# 701_USBHub-Grid-Part2.net
KiCad netlist of a schematic drawn in Altium Designer
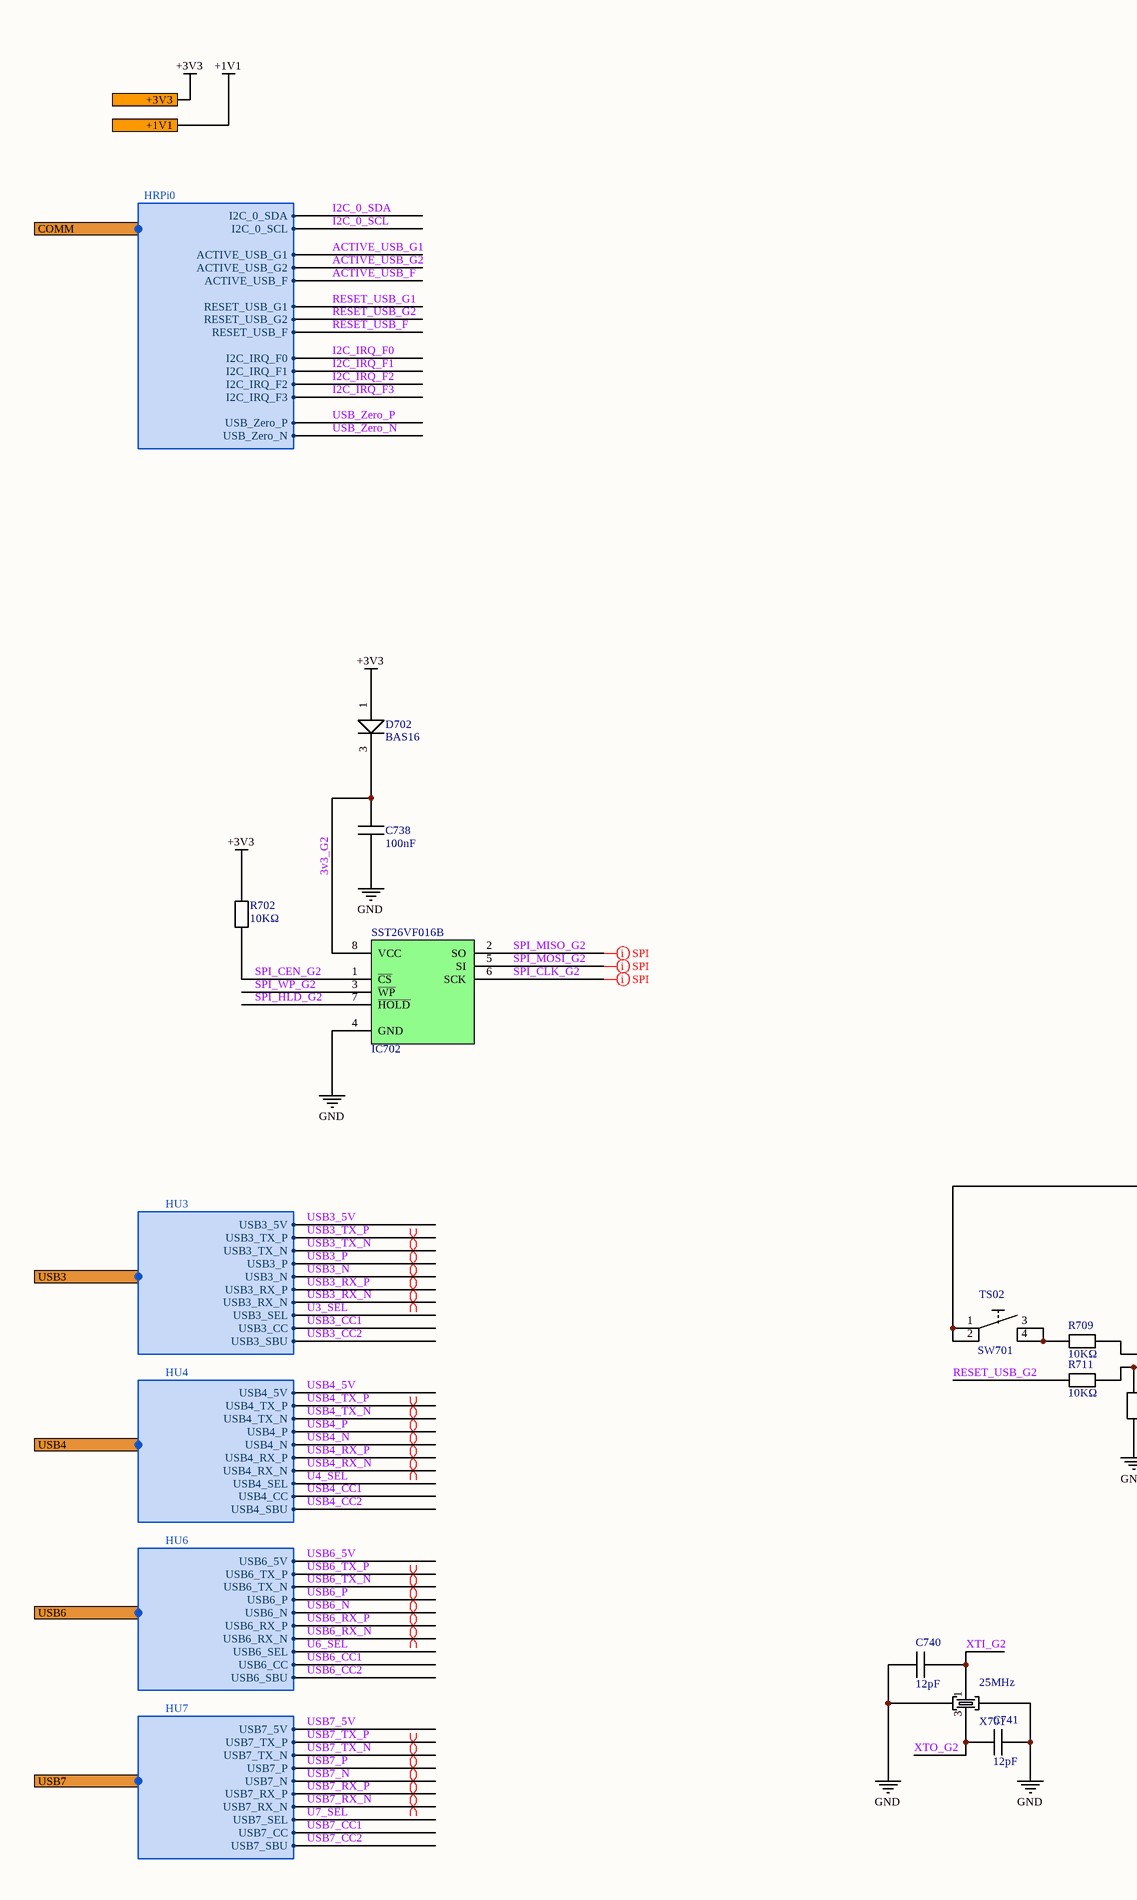
[diagram p0: 701_USBHub-Grid-Part2.SchDoc, left]
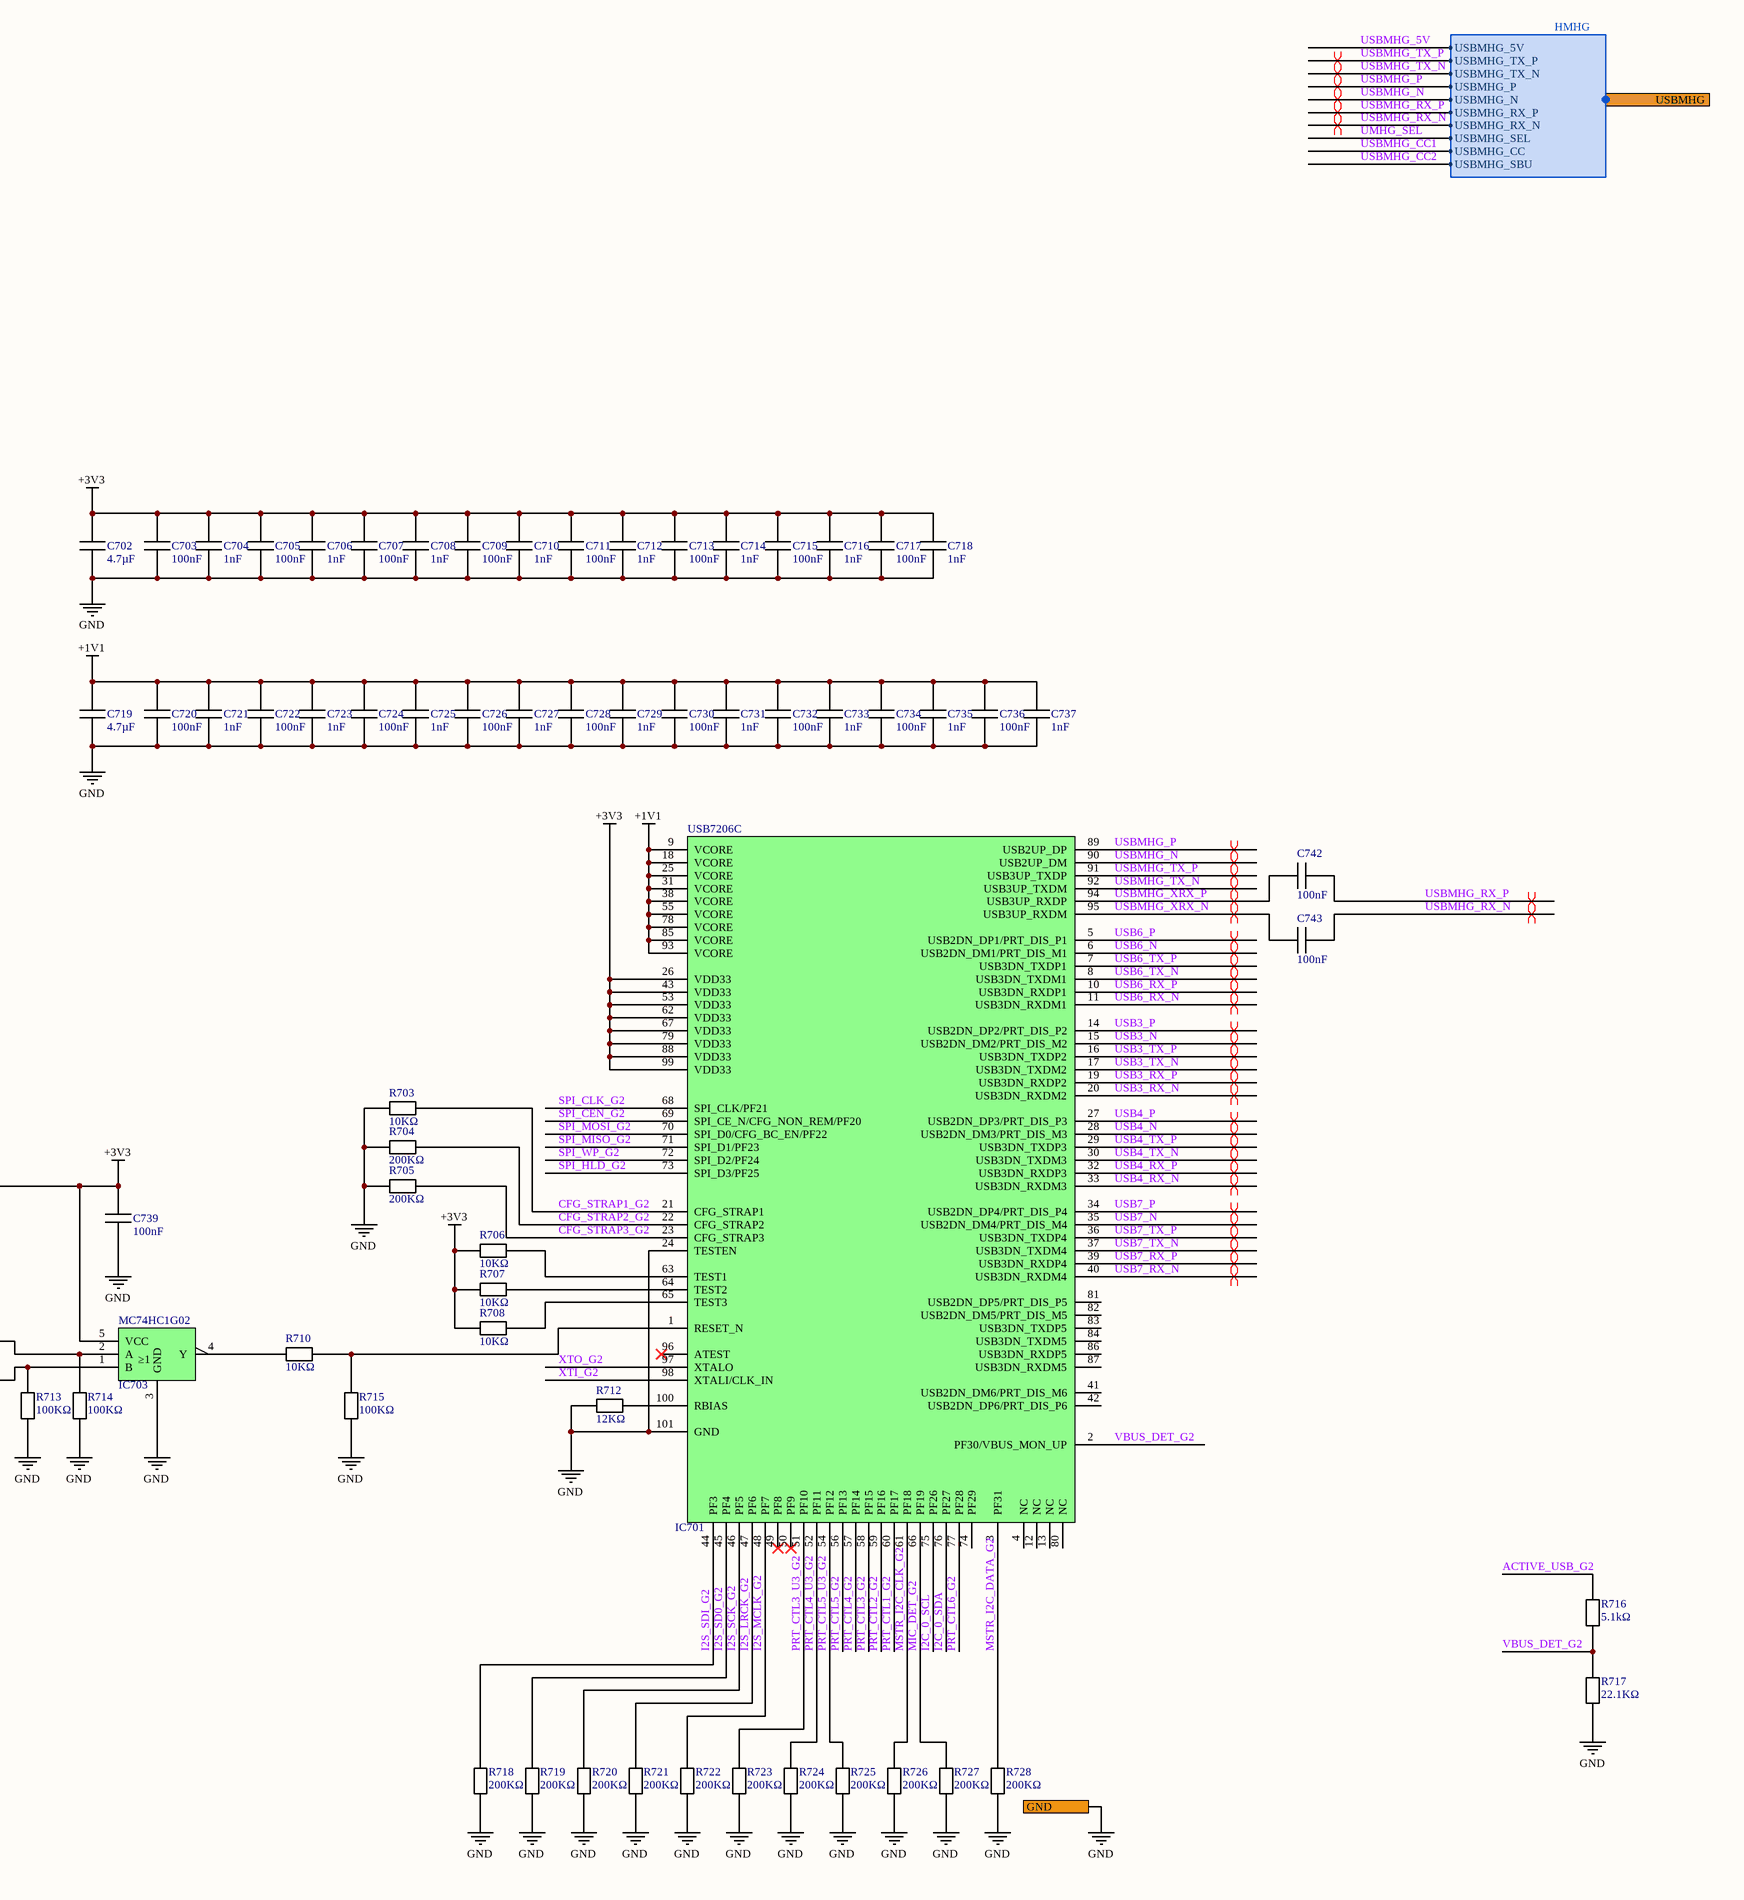
[diagram p1: 701_USBHub-Grid-Part2.SchDoc, right]

(export (version "E")
  (design (tool "Eeschema 10.0.6"))
  (components
    (comp (ref "C702")
      (value "4.7µF")
      (footprint "C0603")
      (description "4.7µF 16V 10% X5R")
      (fields
        (field (name "REFVAL") "4.7µF")
        (field (name "PART NUMBER") "CA0002")
        (field (name "MANFACTPART") "C1608X5R1C475K080AC")
      )
      (libsource (lib "GTS_Database") (part "C"))
    )
    (comp (ref "C703")
      (value "100nF")
      (footprint "C0402")
      (description "100nF 16V 10% X7R")
      (fields
        (field (name "REFVAL") "100nF")
        (field (name "PART NUMBER") "CA0010")
        (field (name "MANFACTPART") "GCM155R71C104KA55D")
      )
      (libsource (lib "GTS_Database") (part "C"))
    )
    (comp (ref "C704")
      (value "1nF")
      (footprint "C0402")
      (description "1nF 50V 1% C0G")
      (fields
        (field (name "REFVAL") "1nF")
        (field (name "PART NUMBER") "CA0031")
        (field (name "MANFACTPART") "GRT1555C1H102FA02D")
      )
      (libsource (lib "GTS_Database") (part "C"))
    )
    (comp (ref "C705")
      (value "100nF")
      (footprint "C0402")
      (description "100nF 16V 10% X7R")
      (fields
        (field (name "REFVAL") "100nF")
        (field (name "PART NUMBER") "CA0010")
        (field (name "MANFACTPART") "GCM155R71C104KA55D")
      )
      (libsource (lib "GTS_Database") (part "C"))
    )
    (comp (ref "C706")
      (value "1nF")
      (footprint "C0402")
      (description "1nF 50V 1% C0G")
      (fields
        (field (name "REFVAL") "1nF")
        (field (name "PART NUMBER") "CA0031")
        (field (name "MANFACTPART") "GRT1555C1H102FA02D")
      )
      (libsource (lib "GTS_Database") (part "C"))
    )
    (comp (ref "C707")
      (value "100nF")
      (footprint "C0402")
      (description "100nF 16V 10% X7R")
      (fields
        (field (name "REFVAL") "100nF")
        (field (name "PART NUMBER") "CA0010")
        (field (name "MANFACTPART") "GCM155R71C104KA55D")
      )
      (libsource (lib "GTS_Database") (part "C"))
    )
    (comp (ref "C708")
      (value "1nF")
      (footprint "C0402")
      (description "1nF 50V 1% C0G")
      (fields
        (field (name "REFVAL") "1nF")
        (field (name "PART NUMBER") "CA0031")
        (field (name "MANFACTPART") "GRT1555C1H102FA02D")
      )
      (libsource (lib "GTS_Database") (part "C"))
    )
    (comp (ref "C709")
      (value "100nF")
      (footprint "C0402")
      (description "100nF 16V 10% X7R")
      (fields
        (field (name "REFVAL") "100nF")
        (field (name "PART NUMBER") "CA0010")
        (field (name "MANFACTPART") "GCM155R71C104KA55D")
      )
      (libsource (lib "GTS_Database") (part "C"))
    )
    (comp (ref "C710")
      (value "1nF")
      (footprint "C0402")
      (description "1nF 50V 1% C0G")
      (fields
        (field (name "REFVAL") "1nF")
        (field (name "PART NUMBER") "CA0031")
        (field (name "MANFACTPART") "GRT1555C1H102FA02D")
      )
      (libsource (lib "GTS_Database") (part "C"))
    )
    (comp (ref "C711")
      (value "100nF")
      (footprint "C0402")
      (description "100nF 16V 10% X7R")
      (fields
        (field (name "REFVAL") "100nF")
        (field (name "PART NUMBER") "CA0010")
        (field (name "MANFACTPART") "GCM155R71C104KA55D")
      )
      (libsource (lib "GTS_Database") (part "C"))
    )
    (comp (ref "C712")
      (value "1nF")
      (footprint "C0402")
      (description "1nF 50V 1% C0G")
      (fields
        (field (name "REFVAL") "1nF")
        (field (name "PART NUMBER") "CA0031")
        (field (name "MANFACTPART") "GRT1555C1H102FA02D")
      )
      (libsource (lib "GTS_Database") (part "C"))
    )
    (comp (ref "C713")
      (value "100nF")
      (footprint "C0402")
      (description "100nF 16V 10% X7R")
      (fields
        (field (name "REFVAL") "100nF")
        (field (name "PART NUMBER") "CA0010")
        (field (name "MANFACTPART") "GCM155R71C104KA55D")
      )
      (libsource (lib "GTS_Database") (part "C"))
    )
    (comp (ref "C714")
      (value "1nF")
      (footprint "C0402")
      (description "1nF 50V 1% C0G")
      (fields
        (field (name "REFVAL") "1nF")
        (field (name "PART NUMBER") "CA0031")
        (field (name "MANFACTPART") "GRT1555C1H102FA02D")
      )
      (libsource (lib "GTS_Database") (part "C"))
    )
    (comp (ref "C715")
      (value "100nF")
      (footprint "C0402")
      (description "100nF 16V 10% X7R")
      (fields
        (field (name "REFVAL") "100nF")
        (field (name "PART NUMBER") "CA0010")
        (field (name "MANFACTPART") "GCM155R71C104KA55D")
      )
      (libsource (lib "GTS_Database") (part "C"))
    )
    (comp (ref "C716")
      (value "1nF")
      (footprint "C0402")
      (description "1nF 50V 1% C0G")
      (fields
        (field (name "REFVAL") "1nF")
        (field (name "PART NUMBER") "CA0031")
        (field (name "MANFACTPART") "GRT1555C1H102FA02D")
      )
      (libsource (lib "GTS_Database") (part "C"))
    )
    (comp (ref "C717")
      (value "100nF")
      (footprint "C0402")
      (description "100nF 16V 10% X7R")
      (fields
        (field (name "REFVAL") "100nF")
        (field (name "PART NUMBER") "CA0010")
        (field (name "MANFACTPART") "GCM155R71C104KA55D")
      )
      (libsource (lib "GTS_Database") (part "C"))
    )
    (comp (ref "C718")
      (value "1nF")
      (footprint "C0402")
      (description "1nF 50V 1% C0G")
      (fields
        (field (name "REFVAL") "1nF")
        (field (name "PART NUMBER") "CA0031")
        (field (name "MANFACTPART") "GRT1555C1H102FA02D")
      )
      (libsource (lib "GTS_Database") (part "C"))
    )
    (comp (ref "C719")
      (value "4.7µF")
      (footprint "C0603")
      (description "4.7µF 16V 10% X5R")
      (fields
        (field (name "REFVAL") "4.7µF")
        (field (name "PART NUMBER") "CA0002")
        (field (name "MANFACTPART") "C1608X5R1C475K080AC")
      )
      (libsource (lib "GTS_Database") (part "C"))
    )
    (comp (ref "C720")
      (value "100nF")
      (footprint "C0402")
      (description "100nF 16V 10% X7R")
      (fields
        (field (name "REFVAL") "100nF")
        (field (name "PART NUMBER") "CA0010")
        (field (name "MANFACTPART") "GCM155R71C104KA55D")
      )
      (libsource (lib "GTS_Database") (part "C"))
    )
    (comp (ref "C721")
      (value "1nF")
      (footprint "C0402")
      (description "1nF 50V 1% C0G")
      (fields
        (field (name "REFVAL") "1nF")
        (field (name "PART NUMBER") "CA0031")
        (field (name "MANFACTPART") "GRT1555C1H102FA02D")
      )
      (libsource (lib "GTS_Database") (part "C"))
    )
    (comp (ref "C722")
      (value "100nF")
      (footprint "C0402")
      (description "100nF 16V 10% X7R")
      (fields
        (field (name "REFVAL") "100nF")
        (field (name "PART NUMBER") "CA0010")
        (field (name "MANFACTPART") "GCM155R71C104KA55D")
      )
      (libsource (lib "GTS_Database") (part "C"))
    )
    (comp (ref "C723")
      (value "1nF")
      (footprint "C0402")
      (description "1nF 50V 1% C0G")
      (fields
        (field (name "REFVAL") "1nF")
        (field (name "PART NUMBER") "CA0031")
        (field (name "MANFACTPART") "GRT1555C1H102FA02D")
      )
      (libsource (lib "GTS_Database") (part "C"))
    )
    (comp (ref "C724")
      (value "100nF")
      (footprint "C0402")
      (description "100nF 16V 10% X7R")
      (fields
        (field (name "REFVAL") "100nF")
        (field (name "PART NUMBER") "CA0010")
        (field (name "MANFACTPART") "GCM155R71C104KA55D")
      )
      (libsource (lib "GTS_Database") (part "C"))
    )
    (comp (ref "C725")
      (value "1nF")
      (footprint "C0402")
      (description "1nF 50V 1% C0G")
      (fields
        (field (name "REFVAL") "1nF")
        (field (name "PART NUMBER") "CA0031")
        (field (name "MANFACTPART") "GRT1555C1H102FA02D")
      )
      (libsource (lib "GTS_Database") (part "C"))
    )
    (comp (ref "C726")
      (value "100nF")
      (footprint "C0402")
      (description "100nF 16V 10% X7R")
      (fields
        (field (name "REFVAL") "100nF")
        (field (name "PART NUMBER") "CA0010")
        (field (name "MANFACTPART") "GCM155R71C104KA55D")
      )
      (libsource (lib "GTS_Database") (part "C"))
    )
    (comp (ref "C727")
      (value "1nF")
      (footprint "C0402")
      (description "1nF 50V 1% C0G")
      (fields
        (field (name "REFVAL") "1nF")
        (field (name "PART NUMBER") "CA0031")
        (field (name "MANFACTPART") "GRT1555C1H102FA02D")
      )
      (libsource (lib "GTS_Database") (part "C"))
    )
    (comp (ref "C728")
      (value "100nF")
      (footprint "C0402")
      (description "100nF 16V 10% X7R")
      (fields
        (field (name "REFVAL") "100nF")
        (field (name "PART NUMBER") "CA0010")
        (field (name "MANFACTPART") "GCM155R71C104KA55D")
      )
      (libsource (lib "GTS_Database") (part "C"))
    )
    (comp (ref "C729")
      (value "1nF")
      (footprint "C0402")
      (description "1nF 50V 1% C0G")
      (fields
        (field (name "REFVAL") "1nF")
        (field (name "PART NUMBER") "CA0031")
        (field (name "MANFACTPART") "GRT1555C1H102FA02D")
      )
      (libsource (lib "GTS_Database") (part "C"))
    )
    (comp (ref "C730")
      (value "100nF")
      (footprint "C0402")
      (description "100nF 16V 10% X7R")
      (fields
        (field (name "REFVAL") "100nF")
        (field (name "PART NUMBER") "CA0010")
        (field (name "MANFACTPART") "GCM155R71C104KA55D")
      )
      (libsource (lib "GTS_Database") (part "C"))
    )
    (comp (ref "C731")
      (value "1nF")
      (footprint "C0402")
      (description "1nF 50V 1% C0G")
      (fields
        (field (name "REFVAL") "1nF")
        (field (name "PART NUMBER") "CA0031")
        (field (name "MANFACTPART") "GRT1555C1H102FA02D")
      )
      (libsource (lib "GTS_Database") (part "C"))
    )
    (comp (ref "C732")
      (value "100nF")
      (footprint "C0402")
      (description "100nF 16V 10% X7R")
      (fields
        (field (name "REFVAL") "100nF")
        (field (name "PART NUMBER") "CA0010")
        (field (name "MANFACTPART") "GCM155R71C104KA55D")
      )
      (libsource (lib "GTS_Database") (part "C"))
    )
    (comp (ref "C733")
      (value "1nF")
      (footprint "C0402")
      (description "1nF 50V 1% C0G")
      (fields
        (field (name "REFVAL") "1nF")
        (field (name "PART NUMBER") "CA0031")
        (field (name "MANFACTPART") "GRT1555C1H102FA02D")
      )
      (libsource (lib "GTS_Database") (part "C"))
    )
    (comp (ref "C734")
      (value "100nF")
      (footprint "C0402")
      (description "100nF 16V 10% X7R")
      (fields
        (field (name "REFVAL") "100nF")
        (field (name "PART NUMBER") "CA0010")
        (field (name "MANFACTPART") "GCM155R71C104KA55D")
      )
      (libsource (lib "GTS_Database") (part "C"))
    )
    (comp (ref "C735")
      (value "1nF")
      (footprint "C0402")
      (description "1nF 50V 1% C0G")
      (fields
        (field (name "REFVAL") "1nF")
        (field (name "PART NUMBER") "CA0031")
        (field (name "MANFACTPART") "GRT1555C1H102FA02D")
      )
      (libsource (lib "GTS_Database") (part "C"))
    )
    (comp (ref "C736")
      (value "100nF")
      (footprint "C0402")
      (description "100nF 16V 10% X7R")
      (fields
        (field (name "REFVAL") "100nF")
        (field (name "PART NUMBER") "CA0010")
        (field (name "MANFACTPART") "GCM155R71C104KA55D")
      )
      (libsource (lib "GTS_Database") (part "C"))
    )
    (comp (ref "C737")
      (value "1nF")
      (footprint "C0402")
      (description "1nF 50V 1% C0G")
      (fields
        (field (name "REFVAL") "1nF")
        (field (name "PART NUMBER") "CA0031")
        (field (name "MANFACTPART") "GRT1555C1H102FA02D")
      )
      (libsource (lib "GTS_Database") (part "C"))
    )
    (comp (ref "C738")
      (value "100nF")
      (footprint "C0402")
      (description "100nF 16V 10% X7R")
      (fields
        (field (name "REFVAL") "100nF")
        (field (name "PART NUMBER") "CA0010")
        (field (name "MANFACTPART") "GCM155R71C104KA55D")
      )
      (libsource (lib "GTS_Database") (part "C"))
    )
    (comp (ref "C739")
      (value "100nF")
      (footprint "C0402")
      (description "100nF 16V 10% X7R")
      (fields
        (field (name "REFVAL") "100nF")
        (field (name "PART NUMBER") "CA0010")
        (field (name "MANFACTPART") "GCM155R71C104KA55D")
      )
      (libsource (lib "GTS_Database") (part "C"))
    )
    (comp (ref "C740")
      (value "12pF")
      (footprint "C0402")
      (description "12pF 16V 1% C0G")
      (fields
        (field (name "REFVAL") "12pF")
        (field (name "PART NUMBER") "CA0059")
        (field (name "MANFACTPART") "VJ0402A120FXJCW1BC")
      )
      (libsource (lib "GTS_Database") (part "C"))
    )
    (comp (ref "C741")
      (value "12pF")
      (footprint "C0402")
      (description "12pF 16V 1% C0G")
      (fields
        (field (name "REFVAL") "12pF")
        (field (name "PART NUMBER") "CA0059")
        (field (name "MANFACTPART") "VJ0402A120FXJCW1BC")
      )
      (libsource (lib "GTS_Database") (part "C"))
    )
    (comp (ref "C742")
      (value "100nF")
      (footprint "C0402")
      (description "100nF 16V 10% X7R")
      (fields
        (field (name "REFVAL") "100nF")
        (field (name "PART NUMBER") "CA0010")
        (field (name "MANFACTPART") "GCM155R71C104KA55D")
      )
      (libsource (lib "GTS_Database") (part "C"))
    )
    (comp (ref "C743")
      (value "100nF")
      (footprint "C0402")
      (description "100nF 16V 10% X7R")
      (fields
        (field (name "REFVAL") "100nF")
        (field (name "PART NUMBER") "CA0010")
        (field (name "MANFACTPART") "GCM155R71C104KA55D")
      )
      (libsource (lib "GTS_Database") (part "C"))
    )
    (comp (ref "D702")
      (value "BAS16")
      (footprint "SOT-23")
      (description "Diodes - General Purpose, Power, Switching 100Vll Signal Switching Diodes 2A")
      (fields
        (field (name "REFVAL") "BAS16")
        (field (name "PART NUMBER") "DI0010")
        (field (name "MANFACTPART") "BAS16_R1_00001")
      )
      (libsource (lib "GTS_Database") (part "Ddefault_3P"))
    )
    (comp (ref "IC701")
      (value "USB7206C")
      (footprint "VQFN-100G_12X12")
      (description "6-Port USB 3.2 Gen 2 Controller Hub")
      (fields (field (name "REFVAL") "USB7206C") (field (name "PART NUMBER") "IC0065"))
      (libsource (lib "GTS_Database") (part "USB7206C"))
    )
    (comp (ref "IC702")
      (value "SST26VF016B")
      (footprint "SO-8")
      (description "16 Mbit Serial Quad I/O (SQI) Flash Memory")
      (fields
        (field (name "REFVAL") "SST26VF016B")
        (field (name "PART NUMBER") "IC0059")
        (field (name "MANFACTPART") "SST26VF016B-104I/SM")
      )
      (libsource (lib "GTS_Database") (part "SST26VF016B"))
    )
    (comp (ref "IC703")
      (value "MC74HC1G02")
      (footprint "TSOP-5")
      (description "Logic Gates 2-6V Single 2-Input NOR")
      (fields
        (field (name "REFVAL") "MC74HC1G02")
        (field (name "PART NUMBER") "IC0061")
        (field (name "MANFACTPART") "MC74HC1G02DTT1G")
      )
      (libsource (lib "GTS_Database") (part "MC74HC1G02"))
    )
    (comp (ref "R702")
      (value "10KΩ")
      (footprint "R0402")
      (description "10KΩ 1% 62.5mW")
      (fields
        (field (name "REFVAL") "10KΩ")
        (field (name "PART NUMBER") "RS0011")
        (field (name "MANFACTPART") "WR04X1002FTL")
      )
      (libsource (lib "GTS_Database") (part "R"))
    )
    (comp (ref "R703")
      (value "10KΩ")
      (footprint "R0402")
      (description "10KΩ 1% 62.5mW")
      (fields
        (field (name "REFVAL") "10KΩ")
        (field (name "PART NUMBER") "RS0011")
        (field (name "MANFACTPART") "WR04X1002FTL")
      )
      (libsource (lib "GTS_Database") (part "R"))
    )
    (comp (ref "R704")
      (value "200KΩ")
      (footprint "R0402")
      (description "200KΩ 1% 62.5mW 100PPM")
      (fields
        (field (name "REFVAL") "200KΩ")
        (field (name "PART NUMBER") "RS0045")
        (field (name "MANFACTPART") "CRG0402F200K")
      )
      (libsource (lib "GTS_Database") (part "R"))
    )
    (comp (ref "R705")
      (value "200KΩ")
      (footprint "R0402")
      (description "200KΩ 1% 62.5mW 100PPM")
      (fields
        (field (name "REFVAL") "200KΩ")
        (field (name "PART NUMBER") "RS0045")
        (field (name "MANFACTPART") "CRG0402F200K")
      )
      (libsource (lib "GTS_Database") (part "R"))
    )
    (comp (ref "R706")
      (value "10KΩ")
      (footprint "R0402")
      (description "10KΩ 1% 62.5mW")
      (fields
        (field (name "REFVAL") "10KΩ")
        (field (name "PART NUMBER") "RS0011")
        (field (name "MANFACTPART") "WR04X1002FTL")
      )
      (libsource (lib "GTS_Database") (part "R"))
    )
    (comp (ref "R707")
      (value "10KΩ")
      (footprint "R0402")
      (description "10KΩ 1% 62.5mW")
      (fields
        (field (name "REFVAL") "10KΩ")
        (field (name "PART NUMBER") "RS0011")
        (field (name "MANFACTPART") "WR04X1002FTL")
      )
      (libsource (lib "GTS_Database") (part "R"))
    )
    (comp (ref "R708")
      (value "10KΩ")
      (footprint "R0402")
      (description "10KΩ 1% 62.5mW")
      (fields
        (field (name "REFVAL") "10KΩ")
        (field (name "PART NUMBER") "RS0011")
        (field (name "MANFACTPART") "WR04X1002FTL")
      )
      (libsource (lib "GTS_Database") (part "R"))
    )
    (comp (ref "R709")
      (value "10KΩ")
      (footprint "R0402")
      (description "10KΩ 1% 62.5mW")
      (fields
        (field (name "REFVAL") "10KΩ")
        (field (name "PART NUMBER") "RS0011")
        (field (name "MANFACTPART") "WR04X1002FTL")
      )
      (libsource (lib "GTS_Database") (part "R"))
    )
    (comp (ref "R710")
      (value "10KΩ")
      (footprint "R0402")
      (description "10KΩ 1% 62.5mW")
      (fields
        (field (name "REFVAL") "10KΩ")
        (field (name "PART NUMBER") "RS0011")
        (field (name "MANFACTPART") "WR04X1002FTL")
      )
      (libsource (lib "GTS_Database") (part "R"))
    )
    (comp (ref "R711")
      (value "10KΩ")
      (footprint "R0402")
      (description "10KΩ 1% 62.5mW")
      (fields
        (field (name "REFVAL") "10KΩ")
        (field (name "PART NUMBER") "RS0011")
        (field (name "MANFACTPART") "WR04X1002FTL")
      )
      (libsource (lib "GTS_Database") (part "R"))
    )
    (comp (ref "R712")
      (value "12KΩ")
      (footprint "R0402")
      (description "12KΩ 1% 62.5mW")
      (fields
        (field (name "REFVAL") "12KΩ")
        (field (name "PART NUMBER") "RS0015")
        (field (name "MANFACTPART") "RC0402FR-1312KL")
      )
      (libsource (lib "GTS_Database") (part "R"))
    )
    (comp (ref "R713")
      (value "100KΩ")
      (footprint "R0402")
      (description "100KΩ 1% 62.5mW 100PPM")
      (fields
        (field (name "REFVAL") "100KΩ")
        (field (name "PART NUMBER") "RS0036")
        (field (name "MANFACTPART") "AC0402FR-13100KL")
      )
      (libsource (lib "GTS_Database") (part "R"))
    )
    (comp (ref "R714")
      (value "100KΩ")
      (footprint "R0402")
      (description "100KΩ 1% 62.5mW 100PPM")
      (fields
        (field (name "REFVAL") "100KΩ")
        (field (name "PART NUMBER") "RS0036")
        (field (name "MANFACTPART") "AC0402FR-13100KL")
      )
      (libsource (lib "GTS_Database") (part "R"))
    )
    (comp (ref "R715")
      (value "100KΩ")
      (footprint "R0402")
      (description "100KΩ 1% 62.5mW 100PPM")
      (fields
        (field (name "REFVAL") "100KΩ")
        (field (name "PART NUMBER") "RS0036")
        (field (name "MANFACTPART") "AC0402FR-13100KL")
      )
      (libsource (lib "GTS_Database") (part "R"))
    )
    (comp (ref "R716")
      (value "5.1kΩ")
      (footprint "R0402")
      (description "5.1KΩ 1% 62.5mW 100PPM")
      (fields
        (field (name "REFVAL") "5.1kΩ")
        (field (name "PART NUMBER") "RS0038")
        (field (name "MANFACTPART") "CRCW04025K10FKEDC")
      )
      (libsource (lib "GTS_Database") (part "R"))
    )
    (comp (ref "R717")
      (value "22.1KΩ")
      (footprint "R0603")
      (description "22.1KΩ 1% 100mW 100PPM")
      (fields
        (field (name "REFVAL") "22.1KΩ")
        (field (name "PART NUMBER") "RS0040")
        (field (name "MANFACTPART") "RC0603FR-0722K1L")
      )
      (libsource (lib "GTS_Database") (part "R"))
    )
    (comp (ref "R718")
      (value "200KΩ")
      (footprint "R0402")
      (description "200KΩ 1% 62.5mW 100PPM")
      (fields
        (field (name "REFVAL") "200KΩ")
        (field (name "PART NUMBER") "RS0045")
        (field (name "MANFACTPART") "CRG0402F200K")
      )
      (libsource (lib "GTS_Database") (part "R"))
    )
    (comp (ref "R719")
      (value "200KΩ")
      (footprint "R0402")
      (description "200KΩ 1% 62.5mW 100PPM")
      (fields
        (field (name "REFVAL") "200KΩ")
        (field (name "PART NUMBER") "RS0045")
        (field (name "MANFACTPART") "CRG0402F200K")
      )
      (libsource (lib "GTS_Database") (part "R"))
    )
    (comp (ref "R720")
      (value "200KΩ")
      (footprint "R0402")
      (description "200KΩ 1% 62.5mW 100PPM")
      (fields
        (field (name "REFVAL") "200KΩ")
        (field (name "PART NUMBER") "RS0045")
        (field (name "MANFACTPART") "CRG0402F200K")
      )
      (libsource (lib "GTS_Database") (part "R"))
    )
    (comp (ref "R721")
      (value "200KΩ")
      (footprint "R0402")
      (description "200KΩ 1% 62.5mW 100PPM")
      (fields
        (field (name "REFVAL") "200KΩ")
        (field (name "PART NUMBER") "RS0045")
        (field (name "MANFACTPART") "CRG0402F200K")
      )
      (libsource (lib "GTS_Database") (part "R"))
    )
    (comp (ref "R722")
      (value "200KΩ")
      (footprint "R0402")
      (description "200KΩ 1% 62.5mW 100PPM")
      (fields
        (field (name "REFVAL") "200KΩ")
        (field (name "PART NUMBER") "RS0045")
        (field (name "MANFACTPART") "CRG0402F200K")
      )
      (libsource (lib "GTS_Database") (part "R"))
    )
    (comp (ref "R723")
      (value "200KΩ")
      (footprint "R0402")
      (description "200KΩ 1% 62.5mW 100PPM")
      (fields
        (field (name "REFVAL") "200KΩ")
        (field (name "PART NUMBER") "RS0045")
        (field (name "MANFACTPART") "CRG0402F200K")
      )
      (libsource (lib "GTS_Database") (part "R"))
    )
    (comp (ref "R724")
      (value "200KΩ")
      (footprint "R0402")
      (description "200KΩ 1% 62.5mW 100PPM")
      (fields
        (field (name "REFVAL") "200KΩ")
        (field (name "PART NUMBER") "RS0045")
        (field (name "MANFACTPART") "CRG0402F200K")
      )
      (libsource (lib "GTS_Database") (part "R"))
    )
    (comp (ref "R725")
      (value "200KΩ")
      (footprint "R0402")
      (description "200KΩ 1% 62.5mW 100PPM")
      (fields
        (field (name "REFVAL") "200KΩ")
        (field (name "PART NUMBER") "RS0045")
        (field (name "MANFACTPART") "CRG0402F200K")
      )
      (libsource (lib "GTS_Database") (part "R"))
    )
    (comp (ref "R726")
      (value "200KΩ")
      (footprint "R0402")
      (description "200KΩ 1% 62.5mW 100PPM")
      (fields
        (field (name "REFVAL") "200KΩ")
        (field (name "PART NUMBER") "RS0045")
        (field (name "MANFACTPART") "CRG0402F200K")
      )
      (libsource (lib "GTS_Database") (part "R"))
    )
    (comp (ref "R727")
      (value "200KΩ")
      (footprint "R0402")
      (description "200KΩ 1% 62.5mW 100PPM")
      (fields
        (field (name "REFVAL") "200KΩ")
        (field (name "PART NUMBER") "RS0045")
        (field (name "MANFACTPART") "CRG0402F200K")
      )
      (libsource (lib "GTS_Database") (part "R"))
    )
    (comp (ref "R728")
      (value "200KΩ")
      (footprint "R0402")
      (description "200KΩ 1% 62.5mW 100PPM")
      (fields
        (field (name "REFVAL") "200KΩ")
        (field (name "PART NUMBER") "RS0045")
        (field (name "MANFACTPART") "CRG0402F200K")
      )
      (libsource (lib "GTS_Database") (part "R"))
    )
    (comp (ref "SW701")
      (value "TS02")
      (footprint "TS02")
      (description "TACTILE SWITCH SPST")
      (fields
        (field (name "REFVAL") "TS02")
        (field (name "PART NUMBER") "SW0005")
        (field (name "MANFACTPART") "TS02-66-50-BK-160-SCR-D")
      )
      (libsource (lib "GTS_Database") (part "SPST-2-4"))
    )
    (comp (ref "X701")
      (value "25MHz")
      (footprint "403W")
      (description "25MHz 8pF 20PPM")
      (fields
        (field (name "REFVAL") "25MHz")
        (field (name "PART NUMBER") "CR0003")
        (field (name "MANFACTPART") "403WF25012IK")
      )
      (libsource (lib "GTS_Database") (part "Crystal_1_3"))
    )
  )
  (nets
    (net (code "7") (name "+1V1") (class "Default")
      (node (ref "C719") (pin "1") (pinfunction "1_1") (pintype "passive"))
      (node (ref "C720") (pin "1") (pinfunction "1_1") (pintype "passive"))
      (node (ref "C721") (pin "1") (pinfunction "1_1") (pintype "passive"))
      (node (ref "C722") (pin "1") (pinfunction "1_1") (pintype "passive"))
      (node (ref "C723") (pin "1") (pinfunction "1_1") (pintype "passive"))
      (node (ref "C724") (pin "1") (pinfunction "1_1") (pintype "passive"))
      (node (ref "C725") (pin "1") (pinfunction "1_1") (pintype "passive"))
      (node (ref "C726") (pin "1") (pinfunction "1_1") (pintype "passive"))
      (node (ref "C727") (pin "1") (pinfunction "1_1") (pintype "passive"))
      (node (ref "C728") (pin "1") (pinfunction "1_1") (pintype "passive"))
      (node (ref "C729") (pin "1") (pinfunction "1_1") (pintype "passive"))
      (node (ref "C730") (pin "1") (pinfunction "1_1") (pintype "passive"))
      (node (ref "C731") (pin "1") (pinfunction "1_1") (pintype "passive"))
      (node (ref "C732") (pin "1") (pinfunction "1_1") (pintype "passive"))
      (node (ref "C733") (pin "1") (pinfunction "1_1") (pintype "passive"))
      (node (ref "C734") (pin "1") (pinfunction "1_1") (pintype "passive"))
      (node (ref "C735") (pin "1") (pinfunction "1_1") (pintype "passive"))
      (node (ref "C736") (pin "1") (pinfunction "1_1") (pintype "passive"))
      (node (ref "C737") (pin "1") (pinfunction "1_1") (pintype "passive"))
      (node (ref "IC701") (pin "18") (pinfunction "VCORE_18") (pintype "passive"))
      (node (ref "IC701") (pin "25") (pinfunction "VCORE_25") (pintype "passive"))
      (node (ref "IC701") (pin "31") (pinfunction "VCORE_31") (pintype "passive"))
      (node (ref "IC701") (pin "38") (pinfunction "VCORE_38") (pintype "passive"))
      (node (ref "IC701") (pin "55") (pinfunction "VCORE_55") (pintype "passive"))
      (node (ref "IC701") (pin "78") (pinfunction "VCORE_78") (pintype "passive"))
      (node (ref "IC701") (pin "85") (pinfunction "VCORE_85") (pintype "passive"))
      (node (ref "IC701") (pin "9") (pinfunction "VCORE_9") (pintype "passive"))
      (node (ref "IC701") (pin "93") (pinfunction "VCORE_93") (pintype "passive"))
    )
    (net (code "8") (name "+3V3") (class "Default")
      (node (ref "C702") (pin "1") (pinfunction "1_1") (pintype "passive"))
      (node (ref "C703") (pin "1") (pinfunction "1_1") (pintype "passive"))
      (node (ref "C704") (pin "1") (pinfunction "1_1") (pintype "passive"))
      (node (ref "C705") (pin "1") (pinfunction "1_1") (pintype "passive"))
      (node (ref "C706") (pin "1") (pinfunction "1_1") (pintype "passive"))
      (node (ref "C707") (pin "1") (pinfunction "1_1") (pintype "passive"))
      (node (ref "C708") (pin "1") (pinfunction "1_1") (pintype "passive"))
      (node (ref "C709") (pin "1") (pinfunction "1_1") (pintype "passive"))
      (node (ref "C710") (pin "1") (pinfunction "1_1") (pintype "passive"))
      (node (ref "C711") (pin "1") (pinfunction "1_1") (pintype "passive"))
      (node (ref "C712") (pin "1") (pinfunction "1_1") (pintype "passive"))
      (node (ref "C713") (pin "1") (pinfunction "1_1") (pintype "passive"))
      (node (ref "C714") (pin "1") (pinfunction "1_1") (pintype "passive"))
      (node (ref "C715") (pin "1") (pinfunction "1_1") (pintype "passive"))
      (node (ref "C716") (pin "1") (pinfunction "1_1") (pintype "passive"))
      (node (ref "C717") (pin "1") (pinfunction "1_1") (pintype "passive"))
      (node (ref "C718") (pin "1") (pinfunction "1_1") (pintype "passive"))
      (node (ref "C739") (pin "1") (pinfunction "1_1") (pintype "passive"))
      (node (ref "D702") (pin "1") (pinfunction "A_1") (pintype "passive"))
      (node (ref "IC701") (pin "26") (pinfunction "VDD33_26") (pintype "passive"))
      (node (ref "IC701") (pin "43") (pinfunction "VDD33_43") (pintype "passive"))
      (node (ref "IC701") (pin "53") (pinfunction "VDD33_53") (pintype "passive"))
      (node (ref "IC701") (pin "62") (pinfunction "VDD33_62") (pintype "passive"))
      (node (ref "IC701") (pin "67") (pinfunction "VDD33_67") (pintype "passive"))
      (node (ref "IC701") (pin "79") (pinfunction "VDD33_79") (pintype "passive"))
      (node (ref "IC701") (pin "88") (pinfunction "VDD33_88") (pintype "passive"))
      (node (ref "IC701") (pin "99") (pinfunction "VDD33_99") (pintype "passive"))
      (node (ref "IC703") (pin "5") (pinfunction "VCC_5") (pintype "passive"))
      (node (ref "R702") (pin "2") (pinfunction "2_2") (pintype "passive"))
      (node (ref "R706") (pin "1") (pinfunction "1_1") (pintype "passive"))
      (node (ref "R707") (pin "1") (pinfunction "1_1") (pintype "passive"))
      (node (ref "R708") (pin "1") (pinfunction "1_1") (pintype "passive"))
      (node (ref "SW701") (pin "1") (pinfunction "1_1") (pintype "passive"))
      (node (ref "SW701") (pin "2") (pinfunction "2_2") (pintype "passive"))
    )
    (net (code "9") (name "/3v3_G2") (class "Default")
      (node (ref "C738") (pin "1") (pinfunction "1_1") (pintype "passive"))
      (node (ref "D702") (pin "3") (pinfunction "K_3") (pintype "passive"))
      (node (ref "IC702") (pin "8") (pinfunction "VCC_8") (pintype "passive"))
    )
    (net (code "12") (name "/ACTIVE_USB_G2") (class "Default")
      (node (ref "R716") (pin "2") (pinfunction "2_2") (pintype "passive"))
    )
    (net (code "13") (name "/CFG_STRAP1_G2") (class "Default")
      (node (ref "IC701") (pin "21") (pinfunction "CFG_STRAP1_21") (pintype "passive"))
      (node (ref "R703") (pin "1") (pinfunction "1_1") (pintype "passive"))
    )
    (net (code "14") (name "/CFG_STRAP2_G2") (class "Default")
      (node (ref "IC701") (pin "22") (pinfunction "CFG_STRAP2_22") (pintype "passive"))
      (node (ref "R704") (pin "2") (pinfunction "2_2") (pintype "passive"))
    )
    (net (code "15") (name "/CFG_STRAP3_G2") (class "Default")
      (node (ref "IC701") (pin "23") (pinfunction "CFG_STRAP3_23") (pintype "passive"))
      (node (ref "R705") (pin "2") (pinfunction "2_2") (pintype "passive"))
    )
    (net (code "16") (name "/I2C_0_SCL") (class "Default")
      (node (ref "IC701") (pin "75") (pinfunction "PF26_75") (pintype "passive"))
    )
    (net (code "17") (name "/I2C_0_SDA") (class "Default")
      (node (ref "IC701") (pin "76") (pinfunction "PF27_76") (pintype "passive"))
    )
    (net (code "22") (name "/I2S_LRCK_G2") (class "Default")
      (node (ref "IC701") (pin "47") (pinfunction "PF6_47") (pintype "passive"))
      (node (ref "R721") (pin "2") (pinfunction "2_2") (pintype "passive"))
    )
    (net (code "23") (name "/I2S_MCLK_G2") (class "Default")
      (node (ref "IC701") (pin "48") (pinfunction "PF7_48") (pintype "passive"))
      (node (ref "R722") (pin "2") (pinfunction "2_2") (pintype "passive"))
    )
    (net (code "24") (name "/I2S_SCK_G2") (class "Default")
      (node (ref "IC701") (pin "46") (pinfunction "PF5_46") (pintype "passive"))
      (node (ref "R720") (pin "2") (pinfunction "2_2") (pintype "passive"))
    )
    (net (code "25") (name "/I2S_SD0_G2") (class "Default")
      (node (ref "IC701") (pin "45") (pinfunction "PF4_45") (pintype "passive"))
      (node (ref "R719") (pin "2") (pinfunction "2_2") (pintype "passive"))
    )
    (net (code "26") (name "/I2S_SDI_G2") (class "Default")
      (node (ref "IC701") (pin "44") (pinfunction "PF3_44") (pintype "passive"))
      (node (ref "R718") (pin "2") (pinfunction "2_2") (pintype "passive"))
    )
    (net (code "27") (name "/MIC_DET_G2") (class "Default")
      (node (ref "IC701") (pin "66") (pinfunction "PF19_66") (pintype "passive"))
      (node (ref "R727") (pin "2") (pinfunction "2_2") (pintype "passive"))
    )
    (net (code "28") (name "/MSTR_I2C_CLK_G2") (class "Default")
      (node (ref "IC701") (pin "61") (pinfunction "PF18_61") (pintype "passive"))
      (node (ref "R726") (pin "2") (pinfunction "2_2") (pintype "passive"))
    )
    (net (code "29") (name "/MSTR_I2C_DATA_G2") (class "Default")
      (node (ref "IC701") (pin "3") (pinfunction "PF31_3") (pintype "passive"))
      (node (ref "R728") (pin "2") (pinfunction "2_2") (pintype "passive"))
    )
    (net (code "30") (name "/PRT_CTL1_G2") (class "Default")
      (node (ref "IC701") (pin "60") (pinfunction "PF17_60") (pintype "passive"))
    )
    (net (code "31") (name "/PRT_CTL2_G2") (class "Default")
      (node (ref "IC701") (pin "59") (pinfunction "PF16_59") (pintype "passive"))
    )
    (net (code "32") (name "/PRT_CTL3_G2") (class "Default")
      (node (ref "IC701") (pin "58") (pinfunction "PF15_58") (pintype "passive"))
    )
    (net (code "33") (name "/PRT_CTL3_U3_G2") (class "Default")
      (node (ref "IC701") (pin "51") (pinfunction "PF10_51") (pintype "passive"))
      (node (ref "R723") (pin "2") (pinfunction "2_2") (pintype "passive"))
    )
    (net (code "34") (name "/PRT_CTL4_G2") (class "Default")
      (node (ref "IC701") (pin "57") (pinfunction "PF14_57") (pintype "passive"))
    )
    (net (code "35") (name "/PRT_CTL4_U3_G2") (class "Default")
      (node (ref "IC701") (pin "52") (pinfunction "PF11_52") (pintype "passive"))
      (node (ref "R724") (pin "2") (pinfunction "2_2") (pintype "passive"))
    )
    (net (code "36") (name "/PRT_CTL5_G2") (class "Default")
      (node (ref "IC701") (pin "56") (pinfunction "PF13_56") (pintype "passive"))
    )
    (net (code "37") (name "/PRT_CTL5_U3_G2") (class "Default")
      (node (ref "IC701") (pin "54") (pinfunction "PF12_54") (pintype "passive"))
      (node (ref "R725") (pin "2") (pinfunction "2_2") (pintype "passive"))
    )
    (net (code "38") (name "/PRT_CTL6_G2") (class "Default")
      (node (ref "IC701") (pin "77") (pinfunction "PF28_77") (pintype "passive"))
    )
    (net (code "41") (name "/RESET_USB_G2") (class "Default")
      (node (ref "R711") (pin "2") (pinfunction "2_2") (pintype "passive"))
    )
    (net (code "42") (name "/SPI_CEN_G2") (class "Default")
      (node (ref "IC701") (pin "69") (pinfunction "SPI_CE_N/CFG_NON_REM/PF20_69") (pintype "passive"))
      (node (ref "IC702") (pin "1") (pinfunction "CS_1") (pintype "passive"))
      (node (ref "R702") (pin "1") (pinfunction "1_1") (pintype "passive"))
    )
    (net (code "43") (name "/SPI_CLK_G2") (class "Default")
      (node (ref "IC701") (pin "68") (pinfunction "SPI_CLK/PF21_68") (pintype "passive"))
      (node (ref "IC702") (pin "6") (pinfunction "SCK_6") (pintype "passive"))
    )
    (net (code "44") (name "/SPI_HLD_G2") (class "Default")
      (node (ref "IC701") (pin "73") (pinfunction "SPI_D3/PF25_73") (pintype "passive"))
      (node (ref "IC702") (pin "7") (pinfunction "HOLD_7") (pintype "passive"))
    )
    (net (code "45") (name "/SPI_MISO_G2") (class "Default")
      (node (ref "IC701") (pin "71") (pinfunction "SPI_D1/PF23_71") (pintype "passive"))
      (node (ref "IC702") (pin "2") (pinfunction "SO_2") (pintype "passive"))
    )
    (net (code "46") (name "/SPI_MOSI_G2") (class "Default")
      (node (ref "IC701") (pin "70") (pinfunction "SPI_D0/CFG_BC_EN/PF22_70") (pintype "passive"))
      (node (ref "IC702") (pin "5") (pinfunction "SI_5") (pintype "passive"))
    )
    (net (code "47") (name "/SPI_WP_G2") (class "Default")
      (node (ref "IC701") (pin "72") (pinfunction "SPI_D2/PF24_72") (pintype "passive"))
      (node (ref "IC702") (pin "3") (pinfunction "WP_3") (pintype "passive"))
    )
    (net (code "56") (name "/USB3_N") (class "Default")
      (node (ref "IC701") (pin "15") (pinfunction "USB2DN_DM2/PRT_DIS_M2_15") (pintype "passive"))
    )
    (net (code "57") (name "/USB3_P") (class "Default")
      (node (ref "IC701") (pin "14") (pinfunction "USB2DN_DP2/PRT_DIS_P2_14") (pintype "passive"))
    )
    (net (code "58") (name "/USB3_RX_N") (class "Default")
      (node (ref "IC701") (pin "20") (pinfunction "USB3DN_RXDM2_20") (pintype "passive"))
    )
    (net (code "59") (name "/USB3_RX_P") (class "Default")
      (node (ref "IC701") (pin "19") (pinfunction "USB3DN_RXDP2_19") (pintype "passive"))
    )
    (net (code "60") (name "/USB3_TX_N") (class "Default")
      (node (ref "IC701") (pin "17") (pinfunction "USB3DN_TXDM2_17") (pintype "passive"))
    )
    (net (code "61") (name "/USB3_TX_P") (class "Default")
      (node (ref "IC701") (pin "16") (pinfunction "USB3DN_TXDP2_16") (pintype "passive"))
    )
    (net (code "65") (name "/USB4_N") (class "Default")
      (node (ref "IC701") (pin "28") (pinfunction "USB2DN_DM3/PRT_DIS_M3_28") (pintype "passive"))
    )
    (net (code "66") (name "/USB4_P") (class "Default")
      (node (ref "IC701") (pin "27") (pinfunction "USB2DN_DP3/PRT_DIS_P3_27") (pintype "passive"))
    )
    (net (code "67") (name "/USB4_RX_N") (class "Default")
      (node (ref "IC701") (pin "33") (pinfunction "USB3DN_RXDM3_33") (pintype "passive"))
    )
    (net (code "68") (name "/USB4_RX_P") (class "Default")
      (node (ref "IC701") (pin "32") (pinfunction "USB3DN_RXDP3_32") (pintype "passive"))
    )
    (net (code "69") (name "/USB4_TX_N") (class "Default")
      (node (ref "IC701") (pin "30") (pinfunction "USB3DN_TXDM3_30") (pintype "passive"))
    )
    (net (code "70") (name "/USB4_TX_P") (class "Default")
      (node (ref "IC701") (pin "29") (pinfunction "USB3DN_TXDP3_29") (pintype "passive"))
    )
    (net (code "74") (name "/USB6_N") (class "Default")
      (node (ref "IC701") (pin "6") (pinfunction "USB2DN_DM1/PRT_DIS_M1_6") (pintype "passive"))
    )
    (net (code "75") (name "/USB6_P") (class "Default")
      (node (ref "IC701") (pin "5") (pinfunction "USB2DN_DP1/PRT_DIS_P1_5") (pintype "passive"))
    )
    (net (code "76") (name "/USB6_RX_N") (class "Default")
      (node (ref "IC701") (pin "11") (pinfunction "USB3DN_RXDM1_11") (pintype "passive"))
    )
    (net (code "77") (name "/USB6_RX_P") (class "Default")
      (node (ref "IC701") (pin "10") (pinfunction "USB3DN_RXDP1_10") (pintype "passive"))
    )
    (net (code "78") (name "/USB6_TX_N") (class "Default")
      (node (ref "IC701") (pin "8") (pinfunction "USB3DN_TXDM1_8") (pintype "passive"))
    )
    (net (code "79") (name "/USB6_TX_P") (class "Default")
      (node (ref "IC701") (pin "7") (pinfunction "USB3DN_TXDP1_7") (pintype "passive"))
    )
    (net (code "83") (name "/USB7_N") (class "Default")
      (node (ref "IC701") (pin "35") (pinfunction "USB2DN_DM4/PRT_DIS_M4_35") (pintype "passive"))
    )
    (net (code "84") (name "/USB7_P") (class "Default")
      (node (ref "IC701") (pin "34") (pinfunction "USB2DN_DP4/PRT_DIS_P4_34") (pintype "passive"))
    )
    (net (code "85") (name "/USB7_RX_N") (class "Default")
      (node (ref "IC701") (pin "40") (pinfunction "USB3DN_RXDM4_40") (pintype "passive"))
    )
    (net (code "86") (name "/USB7_RX_P") (class "Default")
      (node (ref "IC701") (pin "39") (pinfunction "USB3DN_RXDP4_39") (pintype "passive"))
    )
    (net (code "87") (name "/USB7_TX_N") (class "Default")
      (node (ref "IC701") (pin "37") (pinfunction "USB3DN_TXDM4_37") (pintype "passive"))
    )
    (net (code "88") (name "/USB7_TX_P") (class "Default")
      (node (ref "IC701") (pin "36") (pinfunction "USB3DN_TXDP4_36") (pintype "passive"))
    )
    (net (code "92") (name "/USBMHG_N") (class "Default")
      (node (ref "IC701") (pin "90") (pinfunction "USB2UP_DM_90") (pintype "passive"))
    )
    (net (code "93") (name "/USBMHG_P") (class "Default")
      (node (ref "IC701") (pin "89") (pinfunction "USB2UP_DP_89") (pintype "passive"))
    )
    (net (code "94") (name "/USBMHG_RX_N") (class "Default")
      (node (ref "C743") (pin "2") (pinfunction "2_2") (pintype "passive"))
    )
    (net (code "95") (name "/USBMHG_RX_P") (class "Default")
      (node (ref "C742") (pin "2") (pinfunction "2_2") (pintype "passive"))
    )
    (net (code "96") (name "/USBMHG_TX_N") (class "Default")
      (node (ref "IC701") (pin "92") (pinfunction "USB3UP_TXDM_92") (pintype "passive"))
    )
    (net (code "97") (name "/USBMHG_TX_P") (class "Default")
      (node (ref "IC701") (pin "91") (pinfunction "USB3UP_TXDP_91") (pintype "passive"))
    )
    (net (code "98") (name "/USBMHG_XRX_N") (class "Default")
      (node (ref "C743") (pin "1") (pinfunction "1_1") (pintype "passive"))
      (node (ref "IC701") (pin "95") (pinfunction "USB3UP_RXDM_95") (pintype "passive"))
    )
    (net (code "99") (name "/USBMHG_XRX_P") (class "Default")
      (node (ref "C742") (pin "1") (pinfunction "1_1") (pintype "passive"))
      (node (ref "IC701") (pin "94") (pinfunction "USB3UP_RXDP_94") (pintype "passive"))
    )
    (net (code "102") (name "/VBUS_DET_G2") (class "Default")
      (node (ref "IC701") (pin "2") (pinfunction "PF30/VBUS_MON_UP_2") (pintype "passive"))
      (node (ref "R716") (pin "1") (pinfunction "1_1") (pintype "passive"))
      (node (ref "R717") (pin "2") (pinfunction "2_2") (pintype "passive"))
    )
    (net (code "103") (name "/XTI_G2") (class "Default")
      (node (ref "C740") (pin "2") (pinfunction "2_2") (pintype "passive"))
      (node (ref "IC701") (pin "98") (pinfunction "XTALI/CLK_IN_98") (pintype "passive"))
      (node (ref "X701") (pin "1") (pinfunction "1_1") (pintype "passive"))
    )
    (net (code "104") (name "/XTO_G2") (class "Default")
      (node (ref "C741") (pin "1") (pinfunction "1_1") (pintype "passive"))
      (node (ref "IC701") (pin "97") (pinfunction "XTALO_97") (pintype "passive"))
      (node (ref "X701") (pin "3") (pinfunction "3_3") (pintype "passive"))
    )
    (net (code "111") (name "GND") (class "Default")
      (node (ref "C702") (pin "2") (pinfunction "2_2") (pintype "passive"))
      (node (ref "C703") (pin "2") (pinfunction "2_2") (pintype "passive"))
      (node (ref "C704") (pin "2") (pinfunction "2_2") (pintype "passive"))
      (node (ref "C705") (pin "2") (pinfunction "2_2") (pintype "passive"))
      (node (ref "C706") (pin "2") (pinfunction "2_2") (pintype "passive"))
      (node (ref "C707") (pin "2") (pinfunction "2_2") (pintype "passive"))
      (node (ref "C708") (pin "2") (pinfunction "2_2") (pintype "passive"))
      (node (ref "C709") (pin "2") (pinfunction "2_2") (pintype "passive"))
      (node (ref "C710") (pin "2") (pinfunction "2_2") (pintype "passive"))
      (node (ref "C711") (pin "2") (pinfunction "2_2") (pintype "passive"))
      (node (ref "C712") (pin "2") (pinfunction "2_2") (pintype "passive"))
      (node (ref "C713") (pin "2") (pinfunction "2_2") (pintype "passive"))
      (node (ref "C714") (pin "2") (pinfunction "2_2") (pintype "passive"))
      (node (ref "C715") (pin "2") (pinfunction "2_2") (pintype "passive"))
      (node (ref "C716") (pin "2") (pinfunction "2_2") (pintype "passive"))
      (node (ref "C717") (pin "2") (pinfunction "2_2") (pintype "passive"))
      (node (ref "C718") (pin "2") (pinfunction "2_2") (pintype "passive"))
      (node (ref "C719") (pin "2") (pinfunction "2_2") (pintype "passive"))
      (node (ref "C720") (pin "2") (pinfunction "2_2") (pintype "passive"))
      (node (ref "C721") (pin "2") (pinfunction "2_2") (pintype "passive"))
      (node (ref "C722") (pin "2") (pinfunction "2_2") (pintype "passive"))
      (node (ref "C723") (pin "2") (pinfunction "2_2") (pintype "passive"))
      (node (ref "C724") (pin "2") (pinfunction "2_2") (pintype "passive"))
      (node (ref "C725") (pin "2") (pinfunction "2_2") (pintype "passive"))
      (node (ref "C726") (pin "2") (pinfunction "2_2") (pintype "passive"))
      (node (ref "C727") (pin "2") (pinfunction "2_2") (pintype "passive"))
      (node (ref "C728") (pin "2") (pinfunction "2_2") (pintype "passive"))
      (node (ref "C729") (pin "2") (pinfunction "2_2") (pintype "passive"))
      (node (ref "C730") (pin "2") (pinfunction "2_2") (pintype "passive"))
      (node (ref "C731") (pin "2") (pinfunction "2_2") (pintype "passive"))
      (node (ref "C732") (pin "2") (pinfunction "2_2") (pintype "passive"))
      (node (ref "C733") (pin "2") (pinfunction "2_2") (pintype "passive"))
      (node (ref "C734") (pin "2") (pinfunction "2_2") (pintype "passive"))
      (node (ref "C735") (pin "2") (pinfunction "2_2") (pintype "passive"))
      (node (ref "C736") (pin "2") (pinfunction "2_2") (pintype "passive"))
      (node (ref "C737") (pin "2") (pinfunction "2_2") (pintype "passive"))
      (node (ref "C738") (pin "2") (pinfunction "2_2") (pintype "passive"))
      (node (ref "C739") (pin "2") (pinfunction "2_2") (pintype "passive"))
      (node (ref "C740") (pin "1") (pinfunction "1_1") (pintype "passive"))
      (node (ref "C741") (pin "2") (pinfunction "2_2") (pintype "passive"))
      (node (ref "IC701") (pin "101") (pinfunction "GND_101") (pintype "passive"))
      (node (ref "IC701") (pin "24") (pinfunction "TESTEN_24") (pintype "passive"))
      (node (ref "IC702") (pin "4") (pinfunction "GND_4") (pintype "passive"))
      (node (ref "IC703") (pin "3") (pinfunction "GND_3") (pintype "passive"))
      (node (ref "R703") (pin "2") (pinfunction "2_2") (pintype "passive"))
      (node (ref "R704") (pin "1") (pinfunction "1_1") (pintype "passive"))
      (node (ref "R705") (pin "1") (pinfunction "1_1") (pintype "passive"))
      (node (ref "R712") (pin "1") (pinfunction "1_1") (pintype "passive"))
      (node (ref "R713") (pin "1") (pinfunction "1_1") (pintype "passive"))
      (node (ref "R714") (pin "1") (pinfunction "1_1") (pintype "passive"))
      (node (ref "R715") (pin "1") (pinfunction "1_1") (pintype "passive"))
      (node (ref "R717") (pin "1") (pinfunction "1_1") (pintype "passive"))
      (node (ref "R718") (pin "1") (pinfunction "1_1") (pintype "passive"))
      (node (ref "R719") (pin "1") (pinfunction "1_1") (pintype "passive"))
      (node (ref "R720") (pin "1") (pinfunction "1_1") (pintype "passive"))
      (node (ref "R721") (pin "1") (pinfunction "1_1") (pintype "passive"))
      (node (ref "R722") (pin "1") (pinfunction "1_1") (pintype "passive"))
      (node (ref "R723") (pin "1") (pinfunction "1_1") (pintype "passive"))
      (node (ref "R724") (pin "1") (pinfunction "1_1") (pintype "passive"))
      (node (ref "R725") (pin "1") (pinfunction "1_1") (pintype "passive"))
      (node (ref "R726") (pin "1") (pinfunction "1_1") (pintype "passive"))
      (node (ref "R727") (pin "1") (pinfunction "1_1") (pintype "passive"))
      (node (ref "R728") (pin "1") (pinfunction "1_1") (pintype "passive"))
      (node (ref "X701") (pin "2") (pinfunction "2_2") (pintype "passive"))
      (node (ref "X701") (pin "4") (pinfunction "4_4") (pintype "passive"))
    )
    (net (code "112") (name "Net-(IC701-RBIAS)") (class "Default")
      (node (ref "IC701") (pin "100") (pinfunction "RBIAS_100") (pintype "passive"))
      (node (ref "R712") (pin "2") (pinfunction "2_2") (pintype "passive"))
    )
    (net (code "113") (name "Net-(IC701-RESET_N)") (class "Default")
      (node (ref "IC701") (pin "1") (pinfunction "RESET_N_1") (pintype "passive"))
      (node (ref "R710") (pin "2") (pinfunction "2_2") (pintype "passive"))
      (node (ref "R715") (pin "2") (pinfunction "2_2") (pintype "passive"))
    )
    (net (code "114") (name "Net-(IC701-TEST1)") (class "Default")
      (node (ref "IC701") (pin "63") (pinfunction "TEST1_63") (pintype "passive"))
      (node (ref "R706") (pin "2") (pinfunction "2_2") (pintype "passive"))
    )
    (net (code "115") (name "Net-(IC701-TEST2)") (class "Default")
      (node (ref "IC701") (pin "64") (pinfunction "TEST2_64") (pintype "passive"))
      (node (ref "R707") (pin "2") (pinfunction "2_2") (pintype "passive"))
    )
    (net (code "116") (name "Net-(IC701-TEST3)") (class "Default")
      (node (ref "IC701") (pin "65") (pinfunction "TEST3_65") (pintype "passive"))
      (node (ref "R708") (pin "2") (pinfunction "2_2") (pintype "passive"))
    )
    (net (code "117") (name "Net-(IC703-A)") (class "Default")
      (node (ref "IC703") (pin "2") (pinfunction "A_2") (pintype "passive"))
      (node (ref "R709") (pin "1") (pinfunction "1_1") (pintype "passive"))
      (node (ref "R714") (pin "2") (pinfunction "2_2") (pintype "passive"))
    )
    (net (code "118") (name "Net-(IC703-B)") (class "Default")
      (node (ref "IC703") (pin "1") (pinfunction "B_1") (pintype "passive"))
      (node (ref "R711") (pin "1") (pinfunction "1_1") (pintype "passive"))
      (node (ref "R713") (pin "2") (pinfunction "2_2") (pintype "passive"))
    )
    (net (code "119") (name "Net-(IC703-Y)") (class "Default")
      (node (ref "IC703") (pin "4") (pinfunction "Y_4") (pintype "passive"))
      (node (ref "R710") (pin "1") (pinfunction "1_1") (pintype "passive"))
    )
    (net (code "120") (name "Net-(R709-Pad2)") (class "Default")
      (node (ref "R709") (pin "2") (pinfunction "2_2") (pintype "passive"))
      (node (ref "SW701") (pin "3") (pinfunction "3_3") (pintype "passive"))
      (node (ref "SW701") (pin "4") (pinfunction "4_4") (pintype "passive"))
    )
    (net (code "121") (name "unconnected-(IC701-ATEST-Pad96)") (class "Default")
      (node (ref "IC701") (pin "96") (pinfunction "ATEST_96") (pintype "passive+no_connect"))
    )
    (net (code "122") (name "unconnected-(IC701-NC-Pad4)") (class "Default")
      (node (ref "IC701") (pin "4") (pinfunction "NC_4") (pintype "passive"))
    )
    (net (code "123") (name "unconnected-(IC701-NC-Pad12)") (class "Default")
      (node (ref "IC701") (pin "12") (pinfunction "NC_12") (pintype "passive"))
    )
    (net (code "124") (name "unconnected-(IC701-NC-Pad13)") (class "Default")
      (node (ref "IC701") (pin "13") (pinfunction "NC_13") (pintype "passive"))
    )
    (net (code "125") (name "unconnected-(IC701-NC-Pad80)") (class "Default")
      (node (ref "IC701") (pin "80") (pinfunction "NC_80") (pintype "passive"))
    )
    (net (code "126") (name "unconnected-(IC701-PF8-Pad49)") (class "Default")
      (node (ref "IC701") (pin "49") (pinfunction "PF8_49") (pintype "passive+no_connect"))
    )
    (net (code "127") (name "unconnected-(IC701-PF9-Pad50)") (class "Default")
      (node (ref "IC701") (pin "50") (pinfunction "PF9_50") (pintype "passive+no_connect"))
    )
    (net (code "128") (name "unconnected-(IC701-PF29-Pad74)") (class "Default")
      (node (ref "IC701") (pin "74") (pinfunction "PF29_74") (pintype "passive"))
    )
    (net (code "129") (name "unconnected-(IC701-USB2DN_DM5{slash}PRT_DIS_M5-Pad82)") (class "Default")
      (node (ref "IC701") (pin "82") (pinfunction "USB2DN_DM5/PRT_DIS_M5_82") (pintype "passive"))
    )
    (net (code "130") (name "unconnected-(IC701-USB2DN_DM6{slash}PRT_DIS_M6-Pad41)") (class "Default")
      (node (ref "IC701") (pin "41") (pinfunction "USB2DN_DM6/PRT_DIS_M6_41") (pintype "passive"))
    )
    (net (code "131") (name "unconnected-(IC701-USB2DN_DP5{slash}PRT_DIS_P5-Pad81)") (class "Default")
      (node (ref "IC701") (pin "81") (pinfunction "USB2DN_DP5/PRT_DIS_P5_81") (pintype "passive"))
    )
    (net (code "132") (name "unconnected-(IC701-USB2DN_DP6{slash}PRT_DIS_P6-Pad42)") (class "Default")
      (node (ref "IC701") (pin "42") (pinfunction "USB2DN_DP6/PRT_DIS_P6_42") (pintype "passive"))
    )
    (net (code "133") (name "unconnected-(IC701-USB3DN_RXDM5-Pad87)") (class "Default")
      (node (ref "IC701") (pin "87") (pinfunction "USB3DN_RXDM5_87") (pintype "passive"))
    )
    (net (code "134") (name "unconnected-(IC701-USB3DN_RXDP5-Pad86)") (class "Default")
      (node (ref "IC701") (pin "86") (pinfunction "USB3DN_RXDP5_86") (pintype "passive"))
    )
    (net (code "135") (name "unconnected-(IC701-USB3DN_TXDM5-Pad84)") (class "Default")
      (node (ref "IC701") (pin "84") (pinfunction "USB3DN_TXDM5_84") (pintype "passive"))
    )
    (net (code "136") (name "unconnected-(IC701-USB3DN_TXDP5-Pad83)") (class "Default")
      (node (ref "IC701") (pin "83") (pinfunction "USB3DN_TXDP5_83") (pintype "passive"))
    )
  )
)
